# extensionboard.net
KiCad netlist of a schematic drawn in EAGLE
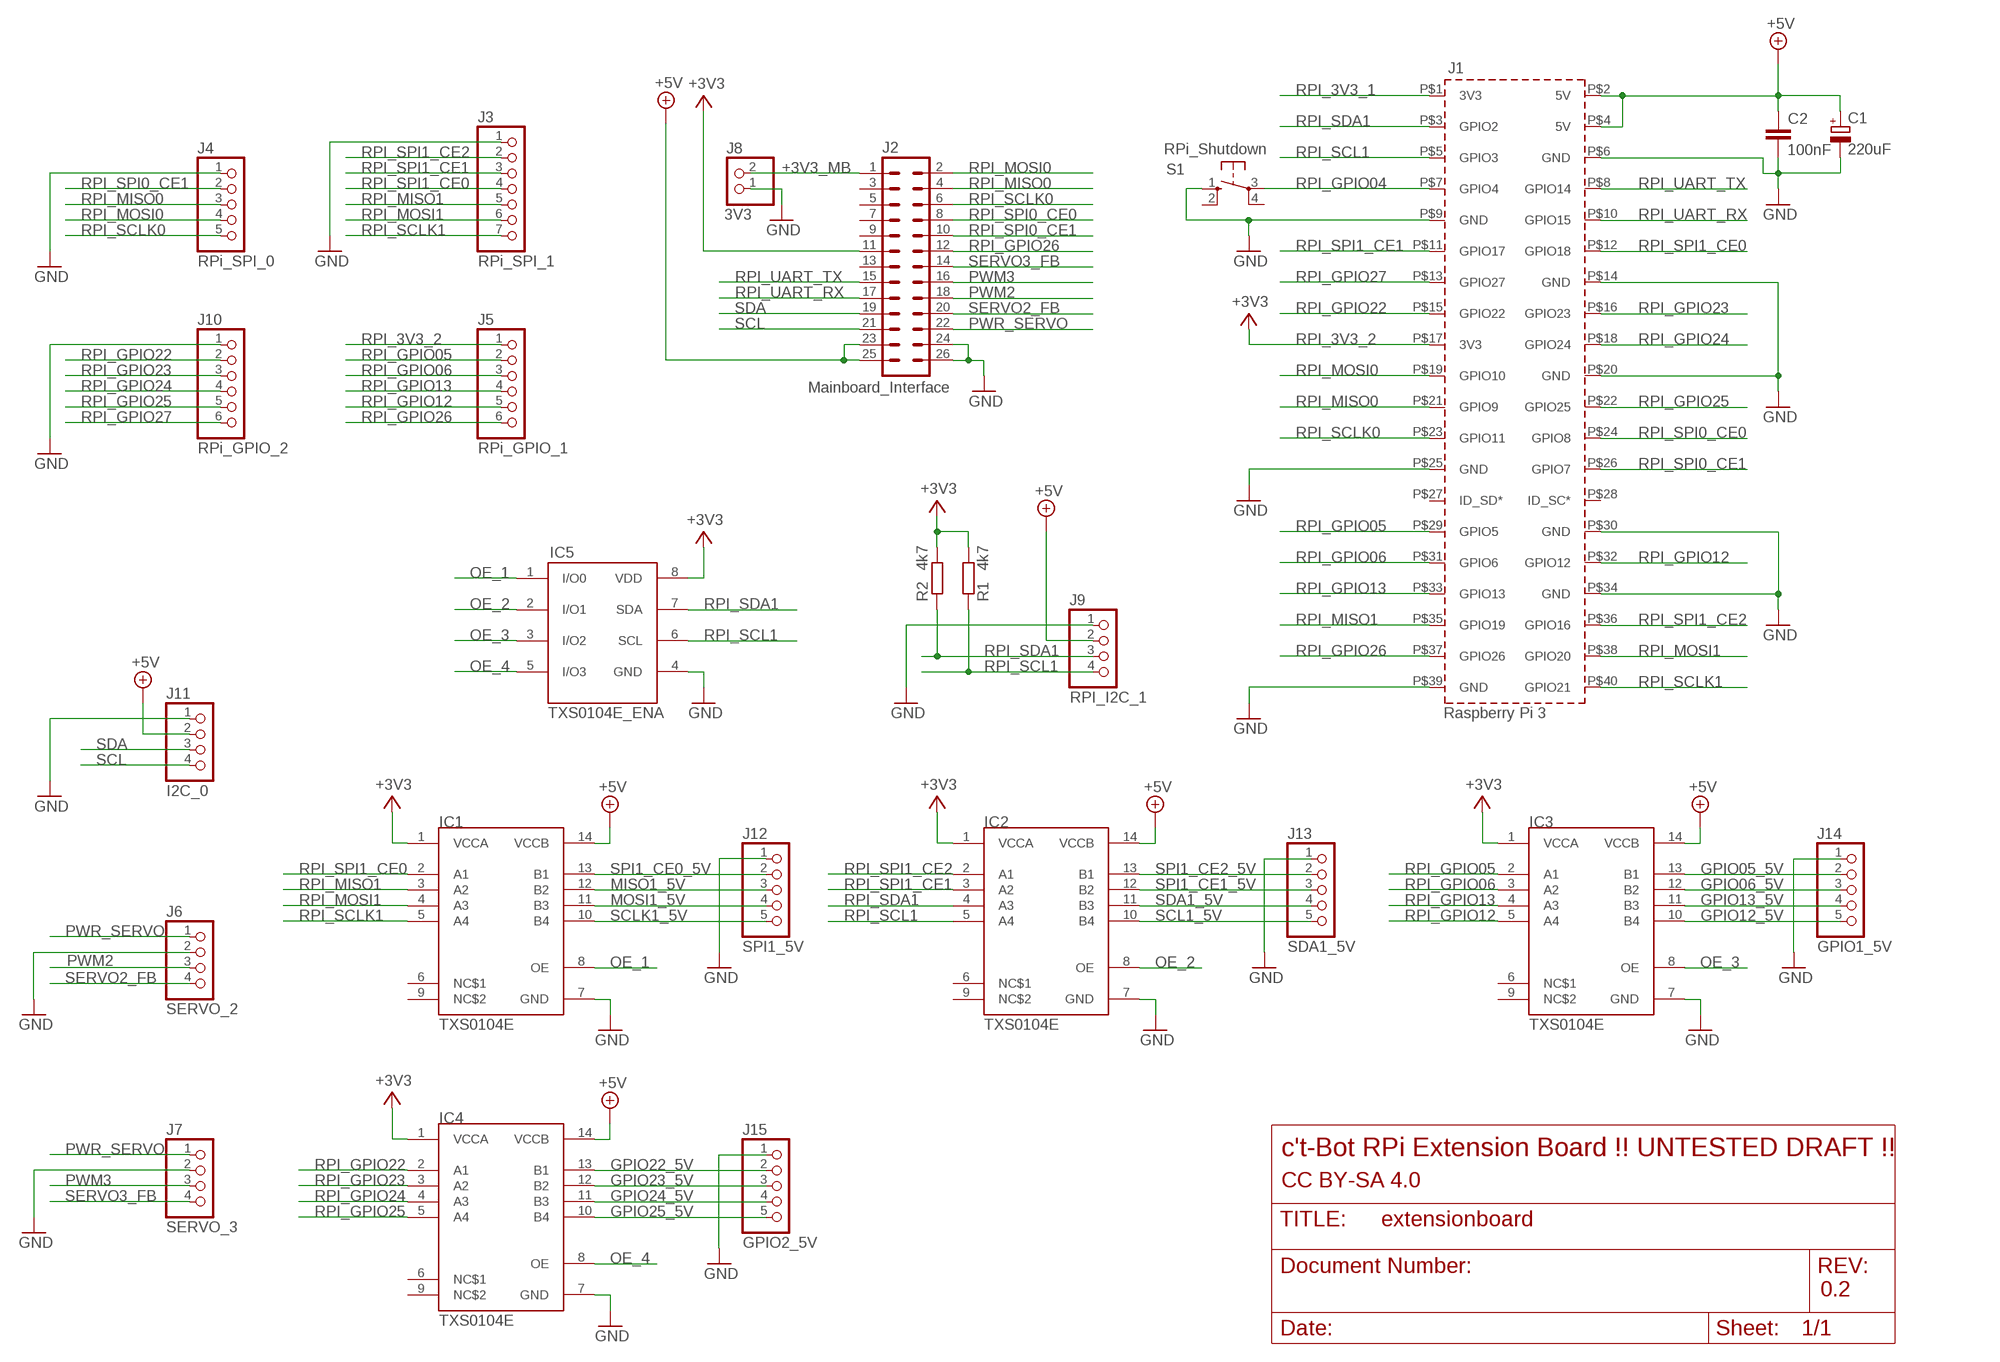
[diagram p0: schematic, sheet 1]

(export (version "E")
  (design (tool "Eeschema 10.0.6"))
  (components
    (comp (ref "C1")
      (value "220uF")
      (footprint "eagle-import:E2,5-6")
      (libsource (lib "eagle-import") (part "CPOL-EUE2.5-6"))
    )
    (comp (ref "C2")
      (value "100nF")
      (footprint "eagle-import:C025-024X044")
      (libsource (lib "eagle-import") (part "C-EU025-024X044"))
    )
    (comp (ref "IC1")
      (value "TXS0104E")
      (footprint "eagle-import:SO14")
      (libsource (lib "eagle-import") (part "TXS0104ED"))
    )
    (comp (ref "IC2")
      (value "TXS0104E")
      (footprint "eagle-import:SO14")
      (libsource (lib "eagle-import") (part "TXS0104ED"))
    )
    (comp (ref "IC3")
      (value "TXS0104E")
      (footprint "eagle-import:SO14")
      (libsource (lib "eagle-import") (part "TXS0104ED"))
    )
    (comp (ref "IC4")
      (value "TXS0104E")
      (footprint "eagle-import:SO14")
      (libsource (lib "eagle-import") (part "TXS0104ED"))
    )
    (comp (ref "IC5")
      (value "TXS0104E_ENA")
      (footprint "eagle-import:SOIC-8")
      (libsource (lib "eagle-import") (part "PCA9536D"))
    )
    (comp (ref "J1")
      (value "Raspberry Pi 3")
      (footprint "eagle-import:RPI3MIRROR")
      (libsource (lib "eagle-import") (part "RPI3RPI3MIRROR"))
    )
    (comp (ref "J2")
      (value "Mainboard_Interface")
      (footprint "eagle-import:ML26")
      (libsource (lib "eagle-import") (part "ML26"))
    )
    (comp (ref "J3")
      (value "RPi_SPI_1")
      (footprint "eagle-import:1X07")
      (libsource (lib "eagle-import") (part "PINHD-1X7"))
    )
    (comp (ref "J4")
      (value "RPi_SPI_0")
      (footprint "eagle-import:1X05")
      (libsource (lib "eagle-import") (part "PINHD-1X5"))
    )
    (comp (ref "J5")
      (value "RPi_GPIO_1")
      (footprint "eagle-import:1X06")
      (libsource (lib "eagle-import") (part "PINHD-1X6"))
    )
    (comp (ref "J6")
      (value "SERVO_2")
      (footprint "eagle-import:1X04")
      (libsource (lib "eagle-import") (part "PINHD-1X4"))
    )
    (comp (ref "J7")
      (value "SERVO_3")
      (footprint "eagle-import:1X04")
      (libsource (lib "eagle-import") (part "PINHD-1X4"))
    )
    (comp (ref "J8")
      (value "3V3")
      (footprint "eagle-import:1X02")
      (libsource (lib "eagle-import") (part "PINHD-1X2"))
    )
    (comp (ref "J9")
      (value "RPI_I2C_1")
      (footprint "eagle-import:1X04")
      (libsource (lib "eagle-import") (part "PINHD-1X4"))
    )
    (comp (ref "J10")
      (value "RPi_GPIO_2")
      (footprint "eagle-import:1X06")
      (libsource (lib "eagle-import") (part "PINHD-1X6"))
    )
    (comp (ref "J11")
      (value "I2C_0")
      (footprint "eagle-import:1X04")
      (libsource (lib "eagle-import") (part "PINHD-1X4"))
    )
    (comp (ref "J12")
      (value "SPI1_5V")
      (footprint "eagle-import:1X05")
      (libsource (lib "eagle-import") (part "PINHD-1X5"))
    )
    (comp (ref "J13")
      (value "SDA1_5V")
      (footprint "eagle-import:1X05")
      (libsource (lib "eagle-import") (part "PINHD-1X5"))
    )
    (comp (ref "J14")
      (value "GPIO1_5V")
      (footprint "eagle-import:1X05")
      (libsource (lib "eagle-import") (part "PINHD-1X5"))
    )
    (comp (ref "J15")
      (value "GPIO2_5V")
      (footprint "eagle-import:1X05")
      (libsource (lib "eagle-import") (part "PINHD-1X5"))
    )
    (comp (ref "R1")
      (value "4k7")
      (footprint "eagle-import:0204_7")
      (libsource (lib "eagle-import") (part "R-EU_0204/7"))
    )
    (comp (ref "R2")
      (value "4k7")
      (footprint "eagle-import:0204_7")
      (libsource (lib "eagle-import") (part "R-EU_0204/7"))
    )
    (comp (ref "S1")
      (value "RPi_Shutdown")
      (footprint "eagle-import:B3F-10XX")
      (fields (field (name "MPN") "B3F-1000"))
      (libsource (lib "eagle-import") (part "10-XX"))
    )
  )
  (nets
    (net (code "1") (name "+3V3") (class "Default")
      (node (ref "IC1") (pin "1") (pinfunction "VCCA_1") (pintype "power_in"))
      (node (ref "IC2") (pin "1") (pinfunction "VCCA_1") (pintype "power_in"))
      (node (ref "IC3") (pin "1") (pinfunction "VCCA_1") (pintype "power_in"))
      (node (ref "IC4") (pin "1") (pinfunction "VCCA_1") (pintype "power_in"))
      (node (ref "IC5") (pin "8") (pinfunction "VDD_8") (pintype "power_in"))
      (node (ref "J1") (pin "P$17") (pinfunction "3V3_P$17") (pintype "bidirectional"))
      (node (ref "J2") (pin "11") (pinfunction "11_11") (pintype "passive"))
      (node (ref "J5") (pin "1") (pinfunction "1_1") (pintype "passive"))
      (node (ref "R1") (pin "2") (pinfunction "2_2") (pintype "passive"))
      (node (ref "R2") (pin "2") (pinfunction "2_2") (pintype "passive"))
    )
    (net (code "2") (name "+5V") (class "Default")
      (node (ref "C1") (pin "+") (pinfunction "+_+") (pintype "passive"))
      (node (ref "C2") (pin "1") (pinfunction "1_1") (pintype "passive"))
      (node (ref "IC1") (pin "14") (pinfunction "VCCB_14") (pintype "power_in"))
      (node (ref "IC2") (pin "14") (pinfunction "VCCB_14") (pintype "power_in"))
      (node (ref "IC3") (pin "14") (pinfunction "VCCB_14") (pintype "power_in"))
      (node (ref "IC4") (pin "14") (pinfunction "VCCB_14") (pintype "power_in"))
      (node (ref "J1") (pin "P$2") (pinfunction "5V_P$2") (pintype "bidirectional"))
      (node (ref "J1") (pin "P$4") (pinfunction "5V_P$4") (pintype "bidirectional"))
      (node (ref "J11") (pin "2") (pinfunction "2_2") (pintype "passive"))
      (node (ref "J2") (pin "23") (pinfunction "23_23") (pintype "passive"))
      (node (ref "J2") (pin "25") (pinfunction "25_25") (pintype "passive"))
      (node (ref "J9") (pin "2") (pinfunction "2_2") (pintype "passive"))
    )
    (net (code "3") (name "/+3V3_MB") (class "Default")
      (node (ref "J2") (pin "1") (pinfunction "1_1") (pintype "passive"))
      (node (ref "J8") (pin "2") (pinfunction "2_2") (pintype "passive"))
    )
    (net (code "4") (name "/GPIO05_5V") (class "Default")
      (node (ref "IC3") (pin "13") (pinfunction "B1_13") (pintype "bidirectional"))
      (node (ref "J14") (pin "2") (pinfunction "2_2") (pintype "passive"))
    )
    (net (code "5") (name "/GPIO06_5V") (class "Default")
      (node (ref "IC3") (pin "12") (pinfunction "B2_12") (pintype "bidirectional"))
      (node (ref "J14") (pin "3") (pinfunction "3_3") (pintype "passive"))
    )
    (net (code "6") (name "/GPIO12_5V") (class "Default")
      (node (ref "IC3") (pin "10") (pinfunction "B4_10") (pintype "bidirectional"))
      (node (ref "J14") (pin "5") (pinfunction "5_5") (pintype "passive"))
    )
    (net (code "7") (name "/GPIO13_5V") (class "Default")
      (node (ref "IC3") (pin "11") (pinfunction "B3_11") (pintype "bidirectional"))
      (node (ref "J14") (pin "4") (pinfunction "4_4") (pintype "passive"))
    )
    (net (code "8") (name "/GPIO22_5V") (class "Default")
      (node (ref "IC4") (pin "13") (pinfunction "B1_13") (pintype "bidirectional"))
      (node (ref "J15") (pin "2") (pinfunction "2_2") (pintype "passive"))
    )
    (net (code "9") (name "/GPIO23_5V") (class "Default")
      (node (ref "IC4") (pin "12") (pinfunction "B2_12") (pintype "bidirectional"))
      (node (ref "J15") (pin "3") (pinfunction "3_3") (pintype "passive"))
    )
    (net (code "10") (name "/GPIO24_5V") (class "Default")
      (node (ref "IC4") (pin "11") (pinfunction "B3_11") (pintype "bidirectional"))
      (node (ref "J15") (pin "4") (pinfunction "4_4") (pintype "passive"))
    )
    (net (code "11") (name "/GPIO25_5V") (class "Default")
      (node (ref "IC4") (pin "10") (pinfunction "B4_10") (pintype "bidirectional"))
      (node (ref "J15") (pin "5") (pinfunction "5_5") (pintype "passive"))
    )
    (net (code "12") (name "/MISO1_5V") (class "Default")
      (node (ref "IC1") (pin "12") (pinfunction "B2_12") (pintype "bidirectional"))
      (node (ref "J12") (pin "3") (pinfunction "3_3") (pintype "passive"))
    )
    (net (code "13") (name "/MOSI1_5V") (class "Default")
      (node (ref "IC1") (pin "11") (pinfunction "B3_11") (pintype "bidirectional"))
      (node (ref "J12") (pin "4") (pinfunction "4_4") (pintype "passive"))
    )
    (net (code "14") (name "/OE_1") (class "Default")
      (node (ref "IC1") (pin "8") (pinfunction "OE_8") (pintype "input"))
      (node (ref "IC5") (pin "1") (pinfunction "I/O0_1") (pintype "bidirectional"))
    )
    (net (code "15") (name "/OE_2") (class "Default")
      (node (ref "IC2") (pin "8") (pinfunction "OE_8") (pintype "input"))
      (node (ref "IC5") (pin "2") (pinfunction "I/O1_2") (pintype "bidirectional"))
    )
    (net (code "16") (name "/OE_3") (class "Default")
      (node (ref "IC3") (pin "8") (pinfunction "OE_8") (pintype "input"))
      (node (ref "IC5") (pin "3") (pinfunction "I/O2_3") (pintype "bidirectional"))
    )
    (net (code "17") (name "/OE_4") (class "Default")
      (node (ref "IC4") (pin "8") (pinfunction "OE_8") (pintype "input"))
      (node (ref "IC5") (pin "5") (pinfunction "I/O3_5") (pintype "bidirectional"))
    )
    (net (code "18") (name "/PWM2") (class "Default")
      (node (ref "J2") (pin "18") (pinfunction "18_18") (pintype "passive"))
      (node (ref "J6") (pin "3") (pinfunction "3_3") (pintype "passive"))
    )
    (net (code "19") (name "/PWM3") (class "Default")
      (node (ref "J2") (pin "16") (pinfunction "16_16") (pintype "passive"))
      (node (ref "J7") (pin "3") (pinfunction "3_3") (pintype "passive"))
    )
    (net (code "20") (name "/PWR_SERVO") (class "Default")
      (node (ref "J2") (pin "22") (pinfunction "22_22") (pintype "passive"))
      (node (ref "J6") (pin "1") (pinfunction "1_1") (pintype "passive"))
      (node (ref "J7") (pin "1") (pinfunction "1_1") (pintype "passive"))
    )
    (net (code "21") (name "/RPI_3V3_1") (class "Default")
      (node (ref "J1") (pin "P$1") (pinfunction "3V3_P$1") (pintype "bidirectional"))
    )
    (net (code "22") (name "/RPI_GPIO04") (class "Default")
      (node (ref "J1") (pin "P$7") (pinfunction "GPIO4_P$7") (pintype "bidirectional"))
      (node (ref "S1") (pin "3") (pinfunction "P_3") (pintype "passive"))
    )
    (net (code "23") (name "/RPI_GPIO05") (class "Default")
      (node (ref "IC3") (pin "2") (pinfunction "A1_2") (pintype "bidirectional"))
      (node (ref "J1") (pin "P$29") (pinfunction "GPIO5_P$29") (pintype "bidirectional"))
      (node (ref "J5") (pin "2") (pinfunction "2_2") (pintype "passive"))
    )
    (net (code "24") (name "/RPI_GPIO06") (class "Default")
      (node (ref "IC3") (pin "3") (pinfunction "A2_3") (pintype "bidirectional"))
      (node (ref "J1") (pin "P$31") (pinfunction "GPIO6_P$31") (pintype "bidirectional"))
      (node (ref "J5") (pin "3") (pinfunction "3_3") (pintype "passive"))
    )
    (net (code "25") (name "/RPI_GPIO12") (class "Default")
      (node (ref "IC3") (pin "5") (pinfunction "A4_5") (pintype "bidirectional"))
      (node (ref "J1") (pin "P$32") (pinfunction "GPIO12_P$32") (pintype "bidirectional"))
      (node (ref "J5") (pin "5") (pinfunction "5_5") (pintype "passive"))
    )
    (net (code "26") (name "/RPI_GPIO13") (class "Default")
      (node (ref "IC3") (pin "4") (pinfunction "A3_4") (pintype "bidirectional"))
      (node (ref "J1") (pin "P$33") (pinfunction "GPIO13_P$33") (pintype "bidirectional"))
      (node (ref "J5") (pin "4") (pinfunction "4_4") (pintype "passive"))
    )
    (net (code "27") (name "/RPI_GPIO22") (class "Default")
      (node (ref "IC4") (pin "2") (pinfunction "A1_2") (pintype "bidirectional"))
      (node (ref "J1") (pin "P$15") (pinfunction "GPIO22_P$15") (pintype "bidirectional"))
      (node (ref "J10") (pin "2") (pinfunction "2_2") (pintype "passive"))
    )
    (net (code "28") (name "/RPI_GPIO23") (class "Default")
      (node (ref "IC4") (pin "3") (pinfunction "A2_3") (pintype "bidirectional"))
      (node (ref "J1") (pin "P$16") (pinfunction "GPIO23_P$16") (pintype "bidirectional"))
      (node (ref "J10") (pin "3") (pinfunction "3_3") (pintype "passive"))
    )
    (net (code "29") (name "/RPI_GPIO24") (class "Default")
      (node (ref "IC4") (pin "4") (pinfunction "A3_4") (pintype "bidirectional"))
      (node (ref "J1") (pin "P$18") (pinfunction "GPIO24_P$18") (pintype "bidirectional"))
      (node (ref "J10") (pin "4") (pinfunction "4_4") (pintype "passive"))
    )
    (net (code "30") (name "/RPI_GPIO25") (class "Default")
      (node (ref "IC4") (pin "5") (pinfunction "A4_5") (pintype "bidirectional"))
      (node (ref "J1") (pin "P$22") (pinfunction "GPIO25_P$22") (pintype "bidirectional"))
      (node (ref "J10") (pin "5") (pinfunction "5_5") (pintype "passive"))
    )
    (net (code "31") (name "/RPI_GPIO26") (class "Default")
      (node (ref "J1") (pin "P$37") (pinfunction "GPIO26_P$37") (pintype "bidirectional"))
      (node (ref "J2") (pin "12") (pinfunction "12_12") (pintype "passive"))
      (node (ref "J5") (pin "6") (pinfunction "6_6") (pintype "passive"))
    )
    (net (code "32") (name "/RPI_GPIO27") (class "Default")
      (node (ref "J1") (pin "P$13") (pinfunction "GPIO27_P$13") (pintype "bidirectional"))
      (node (ref "J10") (pin "6") (pinfunction "6_6") (pintype "passive"))
    )
    (net (code "33") (name "/RPI_MISO0") (class "Default")
      (node (ref "J1") (pin "P$21") (pinfunction "GPIO9_P$21") (pintype "bidirectional"))
      (node (ref "J2") (pin "4") (pinfunction "4_4") (pintype "passive"))
      (node (ref "J4") (pin "3") (pinfunction "3_3") (pintype "passive"))
    )
    (net (code "34") (name "/RPI_MISO1") (class "Default")
      (node (ref "IC1") (pin "3") (pinfunction "A2_3") (pintype "bidirectional"))
      (node (ref "J1") (pin "P$35") (pinfunction "GPIO19_P$35") (pintype "bidirectional"))
      (node (ref "J3") (pin "5") (pinfunction "5_5") (pintype "passive"))
    )
    (net (code "35") (name "/RPI_MOSI0") (class "Default")
      (node (ref "J1") (pin "P$19") (pinfunction "GPIO10_P$19") (pintype "bidirectional"))
      (node (ref "J2") (pin "2") (pinfunction "2_2") (pintype "passive"))
      (node (ref "J4") (pin "4") (pinfunction "4_4") (pintype "passive"))
    )
    (net (code "36") (name "/RPI_MOSI1") (class "Default")
      (node (ref "IC1") (pin "4") (pinfunction "A3_4") (pintype "bidirectional"))
      (node (ref "J1") (pin "P$38") (pinfunction "GPIO20_P$38") (pintype "bidirectional"))
      (node (ref "J3") (pin "6") (pinfunction "6_6") (pintype "passive"))
    )
    (net (code "37") (name "/RPI_SCL1") (class "Default")
      (node (ref "IC2") (pin "5") (pinfunction "A4_5") (pintype "bidirectional"))
      (node (ref "IC5") (pin "6") (pinfunction "SCL_6") (pintype "bidirectional"))
      (node (ref "J1") (pin "P$5") (pinfunction "GPIO3_P$5") (pintype "bidirectional"))
      (node (ref "J9") (pin "4") (pinfunction "4_4") (pintype "passive"))
      (node (ref "R1") (pin "1") (pinfunction "1_1") (pintype "passive"))
    )
    (net (code "38") (name "/RPI_SCLK0") (class "Default")
      (node (ref "J1") (pin "P$23") (pinfunction "GPIO11_P$23") (pintype "bidirectional"))
      (node (ref "J2") (pin "6") (pinfunction "6_6") (pintype "passive"))
      (node (ref "J4") (pin "5") (pinfunction "5_5") (pintype "passive"))
    )
    (net (code "39") (name "/RPI_SCLK1") (class "Default")
      (node (ref "IC1") (pin "5") (pinfunction "A4_5") (pintype "bidirectional"))
      (node (ref "J1") (pin "P$40") (pinfunction "GPIO21_P$40") (pintype "bidirectional"))
      (node (ref "J3") (pin "7") (pinfunction "7_7") (pintype "passive"))
    )
    (net (code "40") (name "/RPI_SDA1") (class "Default")
      (node (ref "IC2") (pin "4") (pinfunction "A3_4") (pintype "bidirectional"))
      (node (ref "IC5") (pin "7") (pinfunction "SDA_7") (pintype "bidirectional"))
      (node (ref "J1") (pin "P$3") (pinfunction "GPIO2_P$3") (pintype "bidirectional"))
      (node (ref "J9") (pin "3") (pinfunction "3_3") (pintype "passive"))
      (node (ref "R2") (pin "1") (pinfunction "1_1") (pintype "passive"))
    )
    (net (code "41") (name "/RPI_SPI0_CE0") (class "Default")
      (node (ref "J1") (pin "P$24") (pinfunction "GPIO8_P$24") (pintype "bidirectional"))
      (node (ref "J2") (pin "8") (pinfunction "8_8") (pintype "passive"))
    )
    (net (code "42") (name "/RPI_SPI0_CE1") (class "Default")
      (node (ref "J1") (pin "P$26") (pinfunction "GPIO7_P$26") (pintype "bidirectional"))
      (node (ref "J2") (pin "10") (pinfunction "10_10") (pintype "passive"))
      (node (ref "J4") (pin "2") (pinfunction "2_2") (pintype "passive"))
    )
    (net (code "43") (name "/RPI_SPI1_CE0") (class "Default")
      (node (ref "IC1") (pin "2") (pinfunction "A1_2") (pintype "bidirectional"))
      (node (ref "J1") (pin "P$12") (pinfunction "GPIO18_P$12") (pintype "bidirectional"))
      (node (ref "J3") (pin "4") (pinfunction "4_4") (pintype "passive"))
    )
    (net (code "44") (name "/RPI_SPI1_CE1") (class "Default")
      (node (ref "IC2") (pin "3") (pinfunction "A2_3") (pintype "bidirectional"))
      (node (ref "J1") (pin "P$11") (pinfunction "GPIO17_P$11") (pintype "bidirectional"))
      (node (ref "J3") (pin "3") (pinfunction "3_3") (pintype "passive"))
    )
    (net (code "45") (name "/RPI_SPI1_CE2") (class "Default")
      (node (ref "IC2") (pin "2") (pinfunction "A1_2") (pintype "bidirectional"))
      (node (ref "J1") (pin "P$36") (pinfunction "GPIO16_P$36") (pintype "bidirectional"))
      (node (ref "J3") (pin "2") (pinfunction "2_2") (pintype "passive"))
    )
    (net (code "46") (name "/RPI_UART_RX") (class "Default")
      (node (ref "J1") (pin "P$10") (pinfunction "GPIO15_P$10") (pintype "bidirectional"))
      (node (ref "J2") (pin "17") (pinfunction "17_17") (pintype "passive"))
    )
    (net (code "47") (name "/RPI_UART_TX") (class "Default")
      (node (ref "J1") (pin "P$8") (pinfunction "GPIO14_P$8") (pintype "bidirectional"))
      (node (ref "J2") (pin "15") (pinfunction "15_15") (pintype "passive"))
    )
    (net (code "48") (name "/SCL") (class "Default")
      (node (ref "J11") (pin "4") (pinfunction "4_4") (pintype "passive"))
      (node (ref "J2") (pin "21") (pinfunction "21_21") (pintype "passive"))
    )
    (net (code "49") (name "/SCL1_5V") (class "Default")
      (node (ref "IC2") (pin "10") (pinfunction "B4_10") (pintype "bidirectional"))
      (node (ref "J13") (pin "5") (pinfunction "5_5") (pintype "passive"))
    )
    (net (code "50") (name "/SCLK1_5V") (class "Default")
      (node (ref "IC1") (pin "10") (pinfunction "B4_10") (pintype "bidirectional"))
      (node (ref "J12") (pin "5") (pinfunction "5_5") (pintype "passive"))
    )
    (net (code "51") (name "/SDA") (class "Default")
      (node (ref "J11") (pin "3") (pinfunction "3_3") (pintype "passive"))
      (node (ref "J2") (pin "19") (pinfunction "19_19") (pintype "passive"))
    )
    (net (code "52") (name "/SDA1_5V") (class "Default")
      (node (ref "IC2") (pin "11") (pinfunction "B3_11") (pintype "bidirectional"))
      (node (ref "J13") (pin "4") (pinfunction "4_4") (pintype "passive"))
    )
    (net (code "53") (name "/SERVO2_FB") (class "Default")
      (node (ref "J2") (pin "20") (pinfunction "20_20") (pintype "passive"))
      (node (ref "J6") (pin "4") (pinfunction "4_4") (pintype "passive"))
    )
    (net (code "54") (name "/SERVO3_FB") (class "Default")
      (node (ref "J2") (pin "14") (pinfunction "14_14") (pintype "passive"))
      (node (ref "J7") (pin "4") (pinfunction "4_4") (pintype "passive"))
    )
    (net (code "55") (name "/SPI1_CE0_5V") (class "Default")
      (node (ref "IC1") (pin "13") (pinfunction "B1_13") (pintype "bidirectional"))
      (node (ref "J12") (pin "2") (pinfunction "2_2") (pintype "passive"))
    )
    (net (code "56") (name "/SPI1_CE1_5V") (class "Default")
      (node (ref "IC2") (pin "12") (pinfunction "B2_12") (pintype "bidirectional"))
      (node (ref "J13") (pin "3") (pinfunction "3_3") (pintype "passive"))
    )
    (net (code "57") (name "/SPI1_CE2_5V") (class "Default")
      (node (ref "IC2") (pin "13") (pinfunction "B1_13") (pintype "bidirectional"))
      (node (ref "J13") (pin "2") (pinfunction "2_2") (pintype "passive"))
    )
    (net (code "58") (name "GND") (class "Default")
      (node (ref "C1") (pin "-") (pinfunction "-_-") (pintype "passive"))
      (node (ref "C2") (pin "2") (pinfunction "2_2") (pintype "passive"))
      (node (ref "IC1") (pin "7") (pinfunction "GND_7") (pintype "power_in"))
      (node (ref "IC2") (pin "7") (pinfunction "GND_7") (pintype "power_in"))
      (node (ref "IC3") (pin "7") (pinfunction "GND_7") (pintype "power_in"))
      (node (ref "IC4") (pin "7") (pinfunction "GND_7") (pintype "power_in"))
      (node (ref "IC5") (pin "4") (pinfunction "GND_4") (pintype "power_in"))
      (node (ref "J1") (pin "P$14") (pinfunction "GND_P$14") (pintype "bidirectional"))
      (node (ref "J1") (pin "P$20") (pinfunction "GND_P$20") (pintype "bidirectional"))
      (node (ref "J1") (pin "P$25") (pinfunction "GND_P$25") (pintype "bidirectional"))
      (node (ref "J1") (pin "P$30") (pinfunction "GND_P$30") (pintype "bidirectional"))
      (node (ref "J1") (pin "P$34") (pinfunction "GND_P$34") (pintype "bidirectional"))
      (node (ref "J1") (pin "P$39") (pinfunction "GND_P$39") (pintype "bidirectional"))
      (node (ref "J1") (pin "P$6") (pinfunction "GND_P$6") (pintype "bidirectional"))
      (node (ref "J1") (pin "P$9") (pinfunction "GND_P$9") (pintype "bidirectional"))
      (node (ref "J10") (pin "1") (pinfunction "1_1") (pintype "passive"))
      (node (ref "J11") (pin "1") (pinfunction "1_1") (pintype "passive"))
      (node (ref "J12") (pin "1") (pinfunction "1_1") (pintype "passive"))
      (node (ref "J13") (pin "1") (pinfunction "1_1") (pintype "passive"))
      (node (ref "J14") (pin "1") (pinfunction "1_1") (pintype "passive"))
      (node (ref "J15") (pin "1") (pinfunction "1_1") (pintype "passive"))
      (node (ref "J2") (pin "24") (pinfunction "24_24") (pintype "passive"))
      (node (ref "J2") (pin "26") (pinfunction "26_26") (pintype "passive"))
      (node (ref "J3") (pin "1") (pinfunction "1_1") (pintype "passive"))
      (node (ref "J4") (pin "1") (pinfunction "1_1") (pintype "passive"))
      (node (ref "J6") (pin "2") (pinfunction "2_2") (pintype "passive"))
      (node (ref "J7") (pin "2") (pinfunction "2_2") (pintype "passive"))
      (node (ref "J8") (pin "1") (pinfunction "1_1") (pintype "passive"))
      (node (ref "J9") (pin "1") (pinfunction "1_1") (pintype "passive"))
      (node (ref "S1") (pin "1") (pinfunction "S_1") (pintype "passive"))
    )
    (net (code "59") (name "unconnected-(IC1-NC$1-Pad6)") (class "Default")
      (node (ref "IC1") (pin "6") (pinfunction "NC$1_6") (pintype "no_connect"))
    )
    (net (code "60") (name "unconnected-(IC1-NC$2-Pad9)") (class "Default")
      (node (ref "IC1") (pin "9") (pinfunction "NC$2_9") (pintype "no_connect"))
    )
    (net (code "61") (name "unconnected-(IC2-NC$1-Pad6)") (class "Default")
      (node (ref "IC2") (pin "6") (pinfunction "NC$1_6") (pintype "no_connect"))
    )
    (net (code "62") (name "unconnected-(IC2-NC$2-Pad9)") (class "Default")
      (node (ref "IC2") (pin "9") (pinfunction "NC$2_9") (pintype "no_connect"))
    )
    (net (code "63") (name "unconnected-(IC3-NC$1-Pad6)") (class "Default")
      (node (ref "IC3") (pin "6") (pinfunction "NC$1_6") (pintype "no_connect"))
    )
    (net (code "64") (name "unconnected-(IC3-NC$2-Pad9)") (class "Default")
      (node (ref "IC3") (pin "9") (pinfunction "NC$2_9") (pintype "no_connect"))
    )
    (net (code "65") (name "unconnected-(IC4-NC$1-Pad6)") (class "Default")
      (node (ref "IC4") (pin "6") (pinfunction "NC$1_6") (pintype "no_connect"))
    )
    (net (code "66") (name "unconnected-(IC4-NC$2-Pad9)") (class "Default")
      (node (ref "IC4") (pin "9") (pinfunction "NC$2_9") (pintype "no_connect"))
    )
    (net (code "67") (name "unconnected-(J1-ID_SC*-PadP$28)") (class "Default")
      (node (ref "J1") (pin "P$28") (pinfunction "ID_SC*_P$28") (pintype "bidirectional"))
    )
    (net (code "68") (name "unconnected-(J1-ID_SD*-PadP$27)") (class "Default")
      (node (ref "J1") (pin "P$27") (pinfunction "ID_SD*_P$27") (pintype "bidirectional"))
    )
    (net (code "69") (name "unconnected-(J2-Pad3)") (class "Default")
      (node (ref "J2") (pin "3") (pinfunction "3_3") (pintype "passive"))
    )
    (net (code "70") (name "unconnected-(J2-Pad5)") (class "Default")
      (node (ref "J2") (pin "5") (pinfunction "5_5") (pintype "passive"))
    )
    (net (code "71") (name "unconnected-(J2-Pad7)") (class "Default")
      (node (ref "J2") (pin "7") (pinfunction "7_7") (pintype "passive"))
    )
    (net (code "72") (name "unconnected-(J2-Pad9)") (class "Default")
      (node (ref "J2") (pin "9") (pinfunction "9_9") (pintype "passive"))
    )
    (net (code "73") (name "unconnected-(J2-Pad13)") (class "Default")
      (node (ref "J2") (pin "13") (pinfunction "13_13") (pintype "passive"))
    )
    (net (code "74") (name "unconnected-(S1-P1-Pad4)") (class "Default")
      (node (ref "S1") (pin "4") (pinfunction "P1_4") (pintype "passive"))
    )
    (net (code "75") (name "unconnected-(S1-S1-Pad2)") (class "Default")
      (node (ref "S1") (pin "2") (pinfunction "S1_2") (pintype "passive"))
    )
  )
)
